# dsPIC.net
KiCad netlist of a schematic drawn in Altium Designer
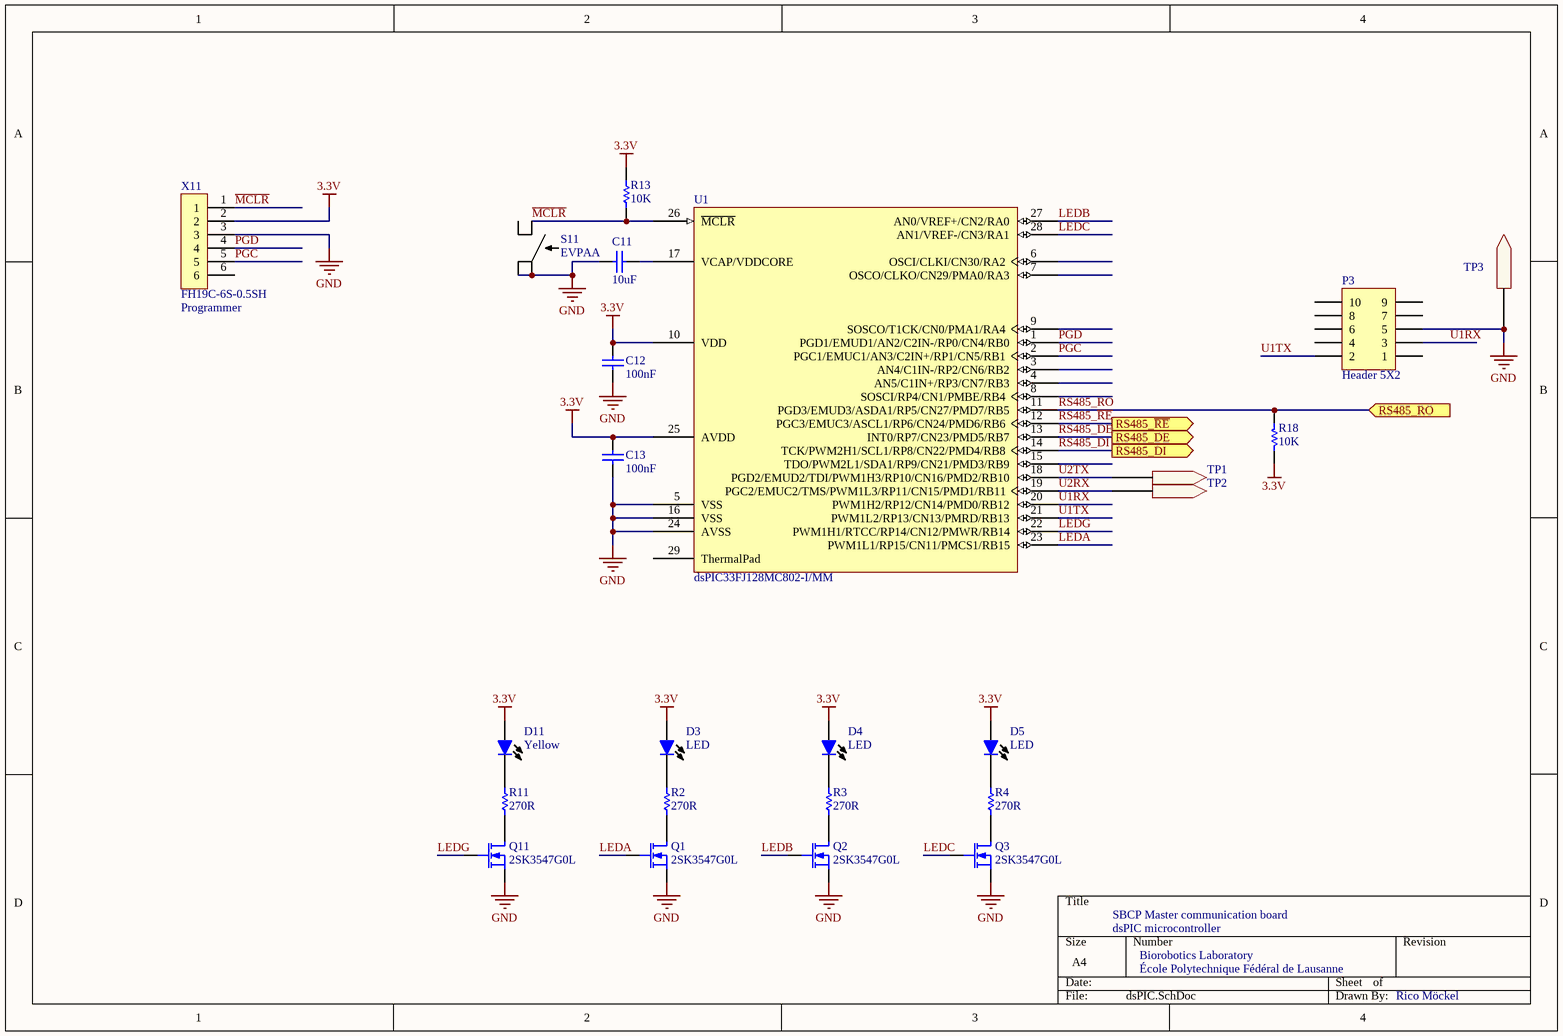
[diagram p0: dsPIC.SchDoc]

(export (version "E")
  (design (tool "Eeschema 10.0.6"))
  (components
    (comp (ref "C11")
      (value "10uF")
      (footprint "CAPC1608N")
      (description "Capacitor")
      (fields (field (name "PUBLISHER") "Altium Limited"))
      (libsource (lib "Miscellaneous Devices") (part "Cap"))
    )
    (comp (ref "C12")
      (value "100nF")
      (footprint "CAPC1005N")
      (description "Capacitor")
      (fields (field (name "PUBLISHER") "Altium Limited"))
      (libsource (lib "Miscellaneous Devices") (part "Cap"))
    )
    (comp (ref "C13")
      (value "100nF")
      (footprint "CAPC1005N")
      (description "Capacitor")
      (fields (field (name "PUBLISHER") "Altium Limited"))
      (libsource (lib "Miscellaneous Devices") (part "Cap"))
    )
    (comp (ref "D3")
      (value "LED Yellow")
      (footprint "RESC1005N")
      (description "LED")
      (fields (field (name "COLOR") "LED"))
      (libsource (lib "Roombots") (part "LED"))
    )
    (comp (ref "D4")
      (value "LED Yellow")
      (footprint "RESC1005N")
      (description "LED")
      (fields (field (name "COLOR") "LED"))
      (libsource (lib "Roombots") (part "LED"))
    )
    (comp (ref "D5")
      (value "LED Yellow")
      (footprint "RESC1005N")
      (description "LED")
      (fields (field (name "COLOR") "LED"))
      (libsource (lib "Roombots") (part "LED"))
    )
    (comp (ref "D11")
      (value "LED Yellow")
      (footprint "RESC1005N")
      (description "LED")
      (fields (field (name "COLOR") "Yellow"))
      (libsource (lib "Roombots") (part "LED"))
    )
    (comp (ref "P3")
      (value "Header 5X2")
      (footprint "HDR2X5")
      (description "Header, 5-Pin, Dual row")
      (fields (field (name "PUBLISHER") "Altium Limited"))
      (libsource (lib "Miscellaneous Connectors") (part "Header 5X2"))
    )
    (comp (ref "Q1")
      (value "2SK3547G0L")
      (footprint "SSS-Mini-3P")
      (description "N-Channel MOSFET 100mA, 50V, 12R")
      (libsource (lib "Roombots") (part "nFET"))
    )
    (comp (ref "Q2")
      (value "2SK3547G0L")
      (footprint "SSS-Mini-3P")
      (description "N-Channel MOSFET 100mA, 50V, 12R")
      (libsource (lib "Roombots") (part "nFET"))
    )
    (comp (ref "Q3")
      (value "2SK3547G0L")
      (footprint "SSS-Mini-3P")
      (description "N-Channel MOSFET 100mA, 50V, 12R")
      (libsource (lib "Roombots") (part "nFET"))
    )
    (comp (ref "Q11")
      (value "2SK3547G0L")
      (footprint "SSS-Mini-3P")
      (description "N-Channel MOSFET 100mA, 50V, 12R")
      (libsource (lib "Roombots") (part "nFET"))
    )
    (comp (ref "R2")
      (value "270R")
      (footprint "RESC1005N")
      (description "Resistor")
      (fields (field (name "PUBLISHER") "Altium Limited"))
      (libsource (lib "Miscellaneous Devices") (part "Res1"))
    )
    (comp (ref "R3")
      (value "270R")
      (footprint "RESC1005N")
      (description "Resistor")
      (fields (field (name "PUBLISHER") "Altium Limited"))
      (libsource (lib "Miscellaneous Devices") (part "Res1"))
    )
    (comp (ref "R4")
      (value "270R")
      (footprint "RESC1005N")
      (description "Resistor")
      (fields (field (name "PUBLISHER") "Altium Limited"))
      (libsource (lib "Miscellaneous Devices") (part "Res1"))
    )
    (comp (ref "R11")
      (value "270R")
      (footprint "RESC1005N")
      (description "Resistor")
      (fields (field (name "PUBLISHER") "Altium Limited"))
      (libsource (lib "Miscellaneous Devices") (part "Res1"))
    )
    (comp (ref "R13")
      (value "10K")
      (footprint "RESC1005N")
      (description "Resistor")
      (fields (field (name "PUBLISHER") "Altium Limited"))
      (libsource (lib "Miscellaneous Devices") (part "Res1"))
    )
    (comp (ref "R18")
      (value "10K")
      (footprint "RESC1005N")
      (description "Resistor")
      (fields (field (name "PUBLISHER") "Altium Limited"))
      (libsource (lib "Miscellaneous Devices") (part "Res1"))
    )
    (comp (ref "S11")
      (value "EVPAA")
      (footprint "EVPAA")
      (description "Push button")
      (libsource (lib "Roombots") (part "Push button"))
    )
    (comp (ref "TP1")
      (value "TP")
      (footprint "TPLOGI")
      (description "Test Point")
      (libsource (lib "Ale") (part "TP"))
    )
    (comp (ref "TP2")
      (value "TP")
      (footprint "TPLOGI")
      (description "Test Point")
      (libsource (lib "Ale") (part "TP"))
    )
    (comp (ref "TP3")
      (value "TP")
      (footprint "TPLOGI")
      (description "Test Point")
      (libsource (lib "Ale") (part "TP"))
    )
    (comp (ref "U1")
      (value "dsPIC33FJ128MC802-I/MM")
      (footprint "QFNS-MM28_M_SmallExp")
      (fields (field (name "PUBLISHER") "Altium Limited"))
      (libsource (lib "Roombots") (part "dsPIC33FJ128MC802-I/MM"))
    )
    (comp (ref "X11")
      (value "FH19C-6S-0.5SH")
      (footprint "FH19C-6S-0.5SH")
      (description "Board to flexible PCB/wire connector")
      (libsource (lib "Roombots") (part "FH19C-6"))
    )
  )
  (nets
    (net (code "1") (name "/LEDA") (class "Default")
      (node (ref "Q1") (pin "G") (pinfunction "G_G") (pintype "passive"))
      (node (ref "U1") (pin "23") (pinfunction "PWM1L1/RP15/CN11/PMCS1/RB15_23") (pintype "bidirectional"))
    )
    (net (code "2") (name "/LEDB") (class "Default")
      (node (ref "Q2") (pin "G") (pinfunction "G_G") (pintype "passive"))
      (node (ref "U1") (pin "27") (pinfunction "AN0/VREF+/CN2/RA0_27") (pintype "bidirectional"))
    )
    (net (code "3") (name "/LEDC") (class "Default")
      (node (ref "Q3") (pin "G") (pinfunction "G_G") (pintype "passive"))
      (node (ref "U1") (pin "28") (pinfunction "AN1/VREF-/CN3/RA1_28") (pintype "bidirectional"))
    )
    (net (code "4") (name "/LEDG") (class "Default")
      (node (ref "Q11") (pin "G") (pinfunction "G_G") (pintype "passive"))
      (node (ref "U1") (pin "22") (pinfunction "PWM1H1/RTCC/RP14/CN12/PMWR/RB14_22") (pintype "bidirectional"))
    )
    (net (code "5") (name "/PGC") (class "Default")
      (node (ref "U1") (pin "2") (pinfunction "PGC1/EMUC1/AN3/C2IN+/RP1/CN5/RB1_2") (pintype "bidirectional"))
      (node (ref "X11") (pin "5") (pinfunction "5_5") (pintype "passive"))
    )
    (net (code "6") (name "/PGD") (class "Default")
      (node (ref "U1") (pin "1") (pinfunction "PGD1/EMUD1/AN2/C2IN-/RP0/CN4/RB0_1") (pintype "bidirectional"))
      (node (ref "X11") (pin "4") (pinfunction "4_4") (pintype "passive"))
    )
    (net (code "7") (name "/RS485_DE") (class "Default")
      (node (ref "U1") (pin "13") (pinfunction "INT0/RP7/CN23/PMD5/RB7_13") (pintype "bidirectional"))
    )
    (net (code "8") (name "/RS485_DI") (class "Default")
      (node (ref "U1") (pin "14") (pinfunction "TCK/PWM2H1/SCL1/RP8/CN22/PMD4/RB8_14") (pintype "bidirectional"))
    )
    (net (code "9") (name "/RS485_RO") (class "Default")
      (node (ref "R18") (pin "2") (pinfunction "2_2") (pintype "passive"))
      (node (ref "U1") (pin "11") (pinfunction "PGD3/EMUD3/ASDA1/RP5/CN27/PMD7/RB5_11") (pintype "bidirectional"))
    )
    (net (code "10") (name "/RS485_~{RE}") (class "Default")
      (node (ref "U1") (pin "12") (pinfunction "PGC3/EMUC3/ASCL1/RP6/CN24/PMD6/RB6_12") (pintype "bidirectional"))
    )
    (net (code "11") (name "/U1RX") (class "Default")
      (node (ref "P3") (pin "3") (pinfunction "3_3") (pintype "passive"))
      (node (ref "U1") (pin "20") (pinfunction "PWM1H2/RP12/CN14/PMD0/RB12_20") (pintype "bidirectional"))
    )
    (net (code "12") (name "/U1TX") (class "Default")
      (node (ref "P3") (pin "2") (pinfunction "2_2") (pintype "passive"))
      (node (ref "U1") (pin "21") (pinfunction "PWM1L2/RP13/CN13/PMRD/RB13_21") (pintype "bidirectional"))
    )
    (net (code "13") (name "/U2RX") (class "Default")
      (node (ref "TP2") (pin "1") (pinfunction "1_1") (pintype "passive"))
      (node (ref "U1") (pin "19") (pinfunction "PGC2/EMUC2/TMS/PWM1L3/RP11/CN15/PMD1/RB11_19") (pintype "bidirectional"))
    )
    (net (code "14") (name "/U2TX") (class "Default")
      (node (ref "TP1") (pin "1") (pinfunction "1_1") (pintype "passive"))
      (node (ref "U1") (pin "18") (pinfunction "PGD2/EMUD2/TDI/PWM1H3/RP10/CN16/PMD2/RB10_18") (pintype "bidirectional"))
    )
    (net (code "15") (name "/~{MCLR}") (class "Default")
      (node (ref "R13") (pin "2") (pinfunction "2_2") (pintype "passive"))
      (node (ref "S11") (pin "2") (pinfunction "2_2") (pintype "passive"))
      (node (ref "U1") (pin "26") (pinfunction "~{MCLR}_26") (pintype "input"))
      (node (ref "X11") (pin "1") (pinfunction "1_1") (pintype "passive"))
    )
    (net (code "16") (name "3.3V") (class "Default")
      (node (ref "C12") (pin "1") (pinfunction "1_1") (pintype "passive"))
      (node (ref "C13") (pin "1") (pinfunction "1_1") (pintype "passive"))
      (node (ref "D11") (pin "1") (pinfunction "A_1") (pintype "passive"))
      (node (ref "D3") (pin "1") (pinfunction "A_1") (pintype "passive"))
      (node (ref "D4") (pin "1") (pinfunction "A_1") (pintype "passive"))
      (node (ref "D5") (pin "1") (pinfunction "A_1") (pintype "passive"))
      (node (ref "R13") (pin "1") (pinfunction "1_1") (pintype "passive"))
      (node (ref "R18") (pin "1") (pinfunction "1_1") (pintype "passive"))
      (node (ref "U1") (pin "10") (pinfunction "VDD_10") (pintype "power_in"))
      (node (ref "U1") (pin "25") (pinfunction "AVDD_25") (pintype "power_in"))
      (node (ref "X11") (pin "2") (pinfunction "2_2") (pintype "passive"))
    )
    (net (code "17") (name "GND") (class "Default")
      (node (ref "C11") (pin "1") (pinfunction "1_1") (pintype "passive"))
      (node (ref "C12") (pin "2") (pinfunction "2_2") (pintype "passive"))
      (node (ref "C13") (pin "2") (pinfunction "2_2") (pintype "passive"))
      (node (ref "P3") (pin "5") (pinfunction "5_5") (pintype "passive"))
      (node (ref "Q1") (pin "S") (pinfunction "S_S") (pintype "passive"))
      (node (ref "Q11") (pin "S") (pinfunction "S_S") (pintype "passive"))
      (node (ref "Q2") (pin "S") (pinfunction "S_S") (pintype "passive"))
      (node (ref "Q3") (pin "S") (pinfunction "S_S") (pintype "passive"))
      (node (ref "S11") (pin "1") (pinfunction "1_1") (pintype "passive"))
      (node (ref "S11") (pin "4") (pinfunction "4_4") (pintype "passive"))
      (node (ref "TP3") (pin "1") (pinfunction "1_1") (pintype "passive"))
      (node (ref "U1") (pin "16") (pinfunction "VSS_16") (pintype "power_in"))
      (node (ref "U1") (pin "24") (pinfunction "AVSS_24") (pintype "power_in"))
      (node (ref "U1") (pin "5") (pinfunction "VSS_5") (pintype "power_in"))
      (node (ref "X11") (pin "3") (pinfunction "3_3") (pintype "passive"))
    )
    (net (code "18") (name "Net-(D3-C)") (class "Default")
      (node (ref "D3") (pin "2") (pinfunction "C_2") (pintype "passive"))
      (node (ref "R2") (pin "1") (pinfunction "1_1") (pintype "passive"))
    )
    (net (code "19") (name "Net-(D4-C)") (class "Default")
      (node (ref "D4") (pin "2") (pinfunction "C_2") (pintype "passive"))
      (node (ref "R3") (pin "1") (pinfunction "1_1") (pintype "passive"))
    )
    (net (code "20") (name "Net-(D5-C)") (class "Default")
      (node (ref "D5") (pin "2") (pinfunction "C_2") (pintype "passive"))
      (node (ref "R4") (pin "1") (pinfunction "1_1") (pintype "passive"))
    )
    (net (code "21") (name "Net-(D11-C)") (class "Default")
      (node (ref "D11") (pin "2") (pinfunction "C_2") (pintype "passive"))
      (node (ref "R11") (pin "1") (pinfunction "1_1") (pintype "passive"))
    )
    (net (code "22") (name "Net-(Q1-PadD)") (class "Default")
      (node (ref "Q1") (pin "D") (pinfunction "D_D") (pintype "passive"))
      (node (ref "R2") (pin "2") (pinfunction "2_2") (pintype "passive"))
    )
    (net (code "23") (name "Net-(Q2-PadD)") (class "Default")
      (node (ref "Q2") (pin "D") (pinfunction "D_D") (pintype "passive"))
      (node (ref "R3") (pin "2") (pinfunction "2_2") (pintype "passive"))
    )
    (net (code "24") (name "Net-(Q3-PadD)") (class "Default")
      (node (ref "Q3") (pin "D") (pinfunction "D_D") (pintype "passive"))
      (node (ref "R4") (pin "2") (pinfunction "2_2") (pintype "passive"))
    )
    (net (code "25") (name "Net-(Q11-PadD)") (class "Default")
      (node (ref "Q11") (pin "D") (pinfunction "D_D") (pintype "passive"))
      (node (ref "R11") (pin "2") (pinfunction "2_2") (pintype "passive"))
    )
    (net (code "26") (name "Net-(U1-VCAP{slash}VDDCORE)") (class "Default")
      (node (ref "C11") (pin "2") (pinfunction "2_2") (pintype "passive"))
      (node (ref "U1") (pin "17") (pinfunction "VCAP/VDDCORE_17") (pintype "power_in"))
    )
    (net (code "27") (name "unconnected-(P3-Pad1)") (class "Default")
      (node (ref "P3") (pin "1") (pinfunction "1_1") (pintype "passive"))
    )
    (net (code "28") (name "unconnected-(P3-Pad4)") (class "Default")
      (node (ref "P3") (pin "4") (pinfunction "4_4") (pintype "passive"))
    )
    (net (code "29") (name "unconnected-(P3-Pad6)") (class "Default")
      (node (ref "P3") (pin "6") (pinfunction "6_6") (pintype "passive"))
    )
    (net (code "30") (name "unconnected-(P3-Pad7)") (class "Default")
      (node (ref "P3") (pin "7") (pinfunction "7_7") (pintype "passive"))
    )
    (net (code "31") (name "unconnected-(P3-Pad8)") (class "Default")
      (node (ref "P3") (pin "8") (pinfunction "8_8") (pintype "passive"))
    )
    (net (code "32") (name "unconnected-(P3-Pad9)") (class "Default")
      (node (ref "P3") (pin "9") (pinfunction "9_9") (pintype "passive"))
    )
    (net (code "33") (name "unconnected-(P3-Pad10)") (class "Default")
      (node (ref "P3") (pin "10") (pinfunction "10_10") (pintype "passive"))
    )
    (net (code "34") (name "unconnected-(S11-Pad3)") (class "Default")
      (node (ref "S11") (pin "3") (pinfunction "3_3") (pintype "passive"))
    )
    (net (code "35") (name "unconnected-(U1-AN4{slash}C1IN-{slash}RP2{slash}CN6{slash}RB2-Pad3)") (class "Default")
      (node (ref "U1") (pin "3") (pinfunction "AN4/C1IN-/RP2/CN6/RB2_3") (pintype "bidirectional"))
    )
    (net (code "36") (name "unconnected-(U1-AN5{slash}C1IN+{slash}RP3{slash}CN7{slash}RB3-Pad4)") (class "Default")
      (node (ref "U1") (pin "4") (pinfunction "AN5/C1IN+/RP3/CN7/RB3_4") (pintype "bidirectional"))
    )
    (net (code "37") (name "unconnected-(U1-OSCI{slash}CLKI{slash}CN30{slash}RA2-Pad6)") (class "Default")
      (node (ref "U1") (pin "6") (pinfunction "OSCI/CLKI/CN30/RA2_6") (pintype "bidirectional"))
    )
    (net (code "38") (name "unconnected-(U1-OSCO{slash}CLKO{slash}CN29{slash}PMA0{slash}RA3-Pad7)") (class "Default")
      (node (ref "U1") (pin "7") (pinfunction "OSCO/CLKO/CN29/PMA0/RA3_7") (pintype "bidirectional"))
    )
    (net (code "39") (name "unconnected-(U1-SOSCI{slash}RP4{slash}CN1{slash}PMBE{slash}RB4-Pad8)") (class "Default")
      (node (ref "U1") (pin "8") (pinfunction "SOSCI/RP4/CN1/PMBE/RB4_8") (pintype "bidirectional"))
    )
    (net (code "40") (name "unconnected-(U1-SOSCO{slash}T1CK{slash}CN0{slash}PMA1{slash}RA4-Pad9)") (class "Default")
      (node (ref "U1") (pin "9") (pinfunction "SOSCO/T1CK/CN0/PMA1/RA4_9") (pintype "bidirectional"))
    )
    (net (code "41") (name "unconnected-(U1-TDO{slash}PWM2L1{slash}SDA1{slash}RP9{slash}CN21{slash}PMD3{slash}RB9-Pad15)") (class "Default")
      (node (ref "U1") (pin "15") (pinfunction "TDO/PWM2L1/SDA1/RP9/CN21/PMD3/RB9_15") (pintype "bidirectional"))
    )
    (net (code "42") (name "unconnected-(U1-ThermalPad-Pad29)") (class "Default")
      (node (ref "U1") (pin "29") (pinfunction "ThermalPad_29") (pintype "passive"))
    )
    (net (code "43") (name "unconnected-(X11-Pad6)") (class "Default")
      (node (ref "X11") (pin "6") (pinfunction "6_6") (pintype "passive"))
    )
  )
)
